# SurfaceControlSystem_RevA.net
KiCad netlist of a schematic drawn in Altium Designer
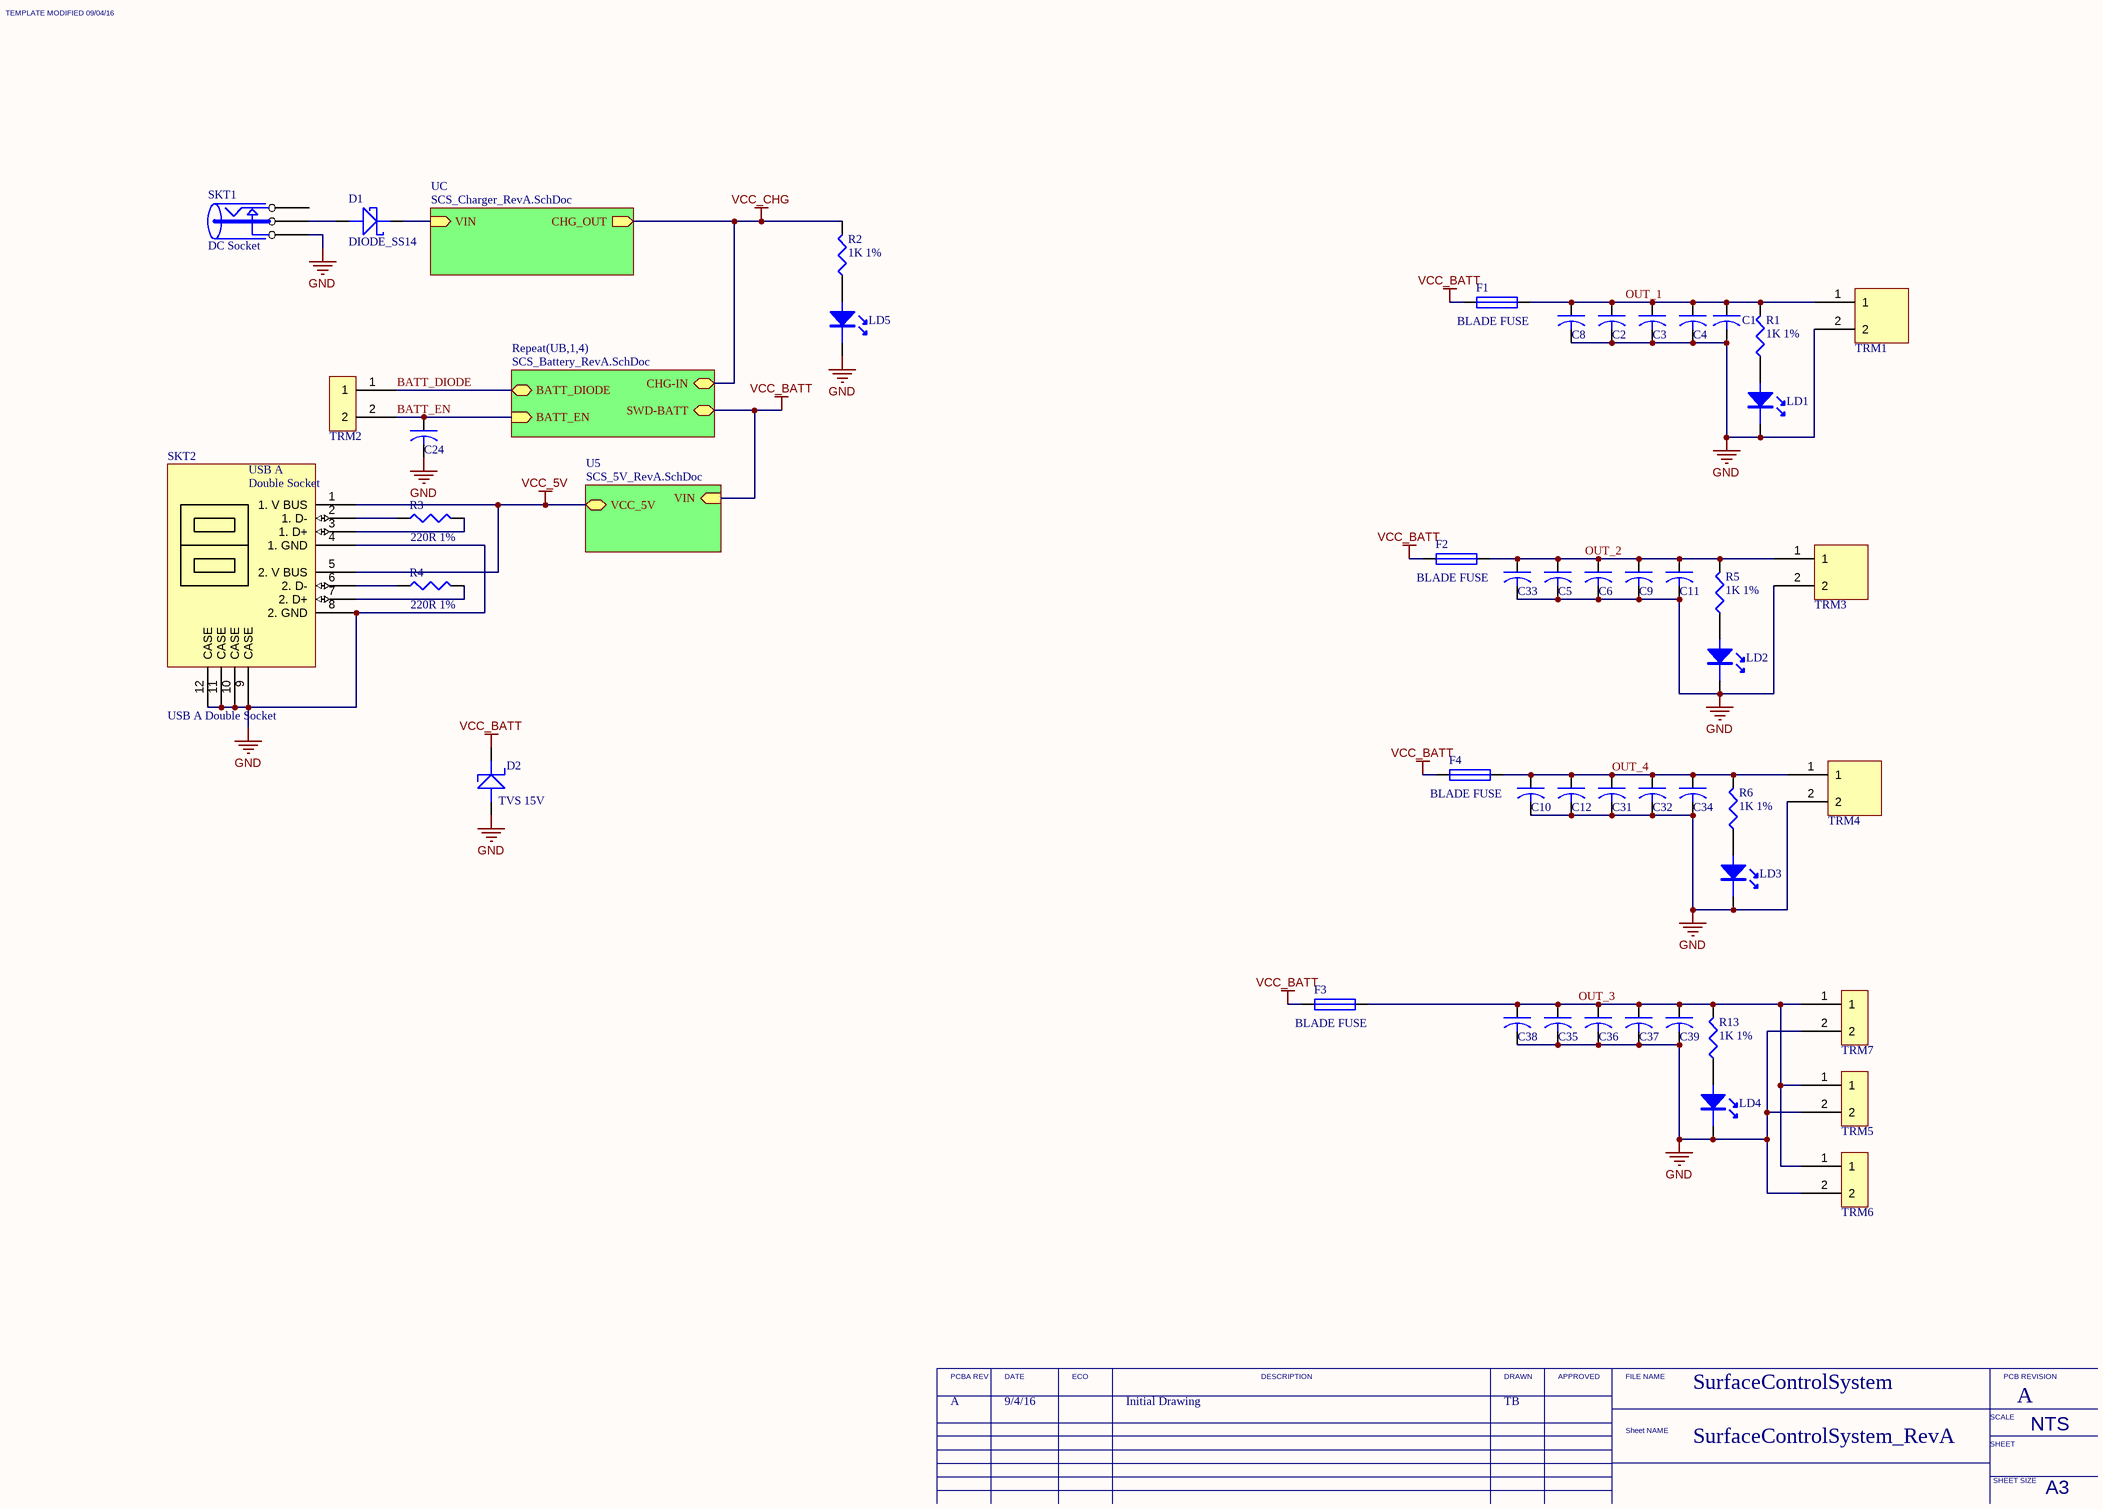
[diagram p0: SurfaceControlSystem_RevA.SchDoc]

(export (version "E")
  (design (tool "Eeschema 10.0.6"))
  (components
    (comp (ref "C1")
      (value "10UF 25V")
      (footprint "1206")
      (description "CAP CER 10UF 25V 10% X5R 1206")
      (fields (field (name "MANUFACTURER") "Murata"))
      (libsource (lib "Caps") (part "CAP_10UF_25V_10%_1206"))
    )
    (comp (ref "C2")
      (value "10UF 25V")
      (footprint "1206")
      (description "CAP CER 10UF 25V 10% X5R 1206")
      (fields (field (name "MANUFACTURER") "Murata"))
      (libsource (lib "Caps") (part "CAP_10UF_25V_10%_1206"))
    )
    (comp (ref "C3")
      (value "10UF 25V")
      (footprint "1206")
      (description "CAP CER 10UF 25V 10% X5R 1206")
      (fields (field (name "MANUFACTURER") "Murata"))
      (libsource (lib "Caps") (part "CAP_10UF_25V_10%_1206"))
    )
    (comp (ref "C4")
      (value "10UF 25V")
      (footprint "1206")
      (description "CAP CER 10UF 25V 10% X5R 1206")
      (fields (field (name "MANUFACTURER") "Murata"))
      (libsource (lib "Caps") (part "CAP_10UF_25V_10%_1206"))
    )
    (comp (ref "C5")
      (value "10UF 25V")
      (footprint "1206")
      (description "CAP CER 10UF 25V 10% X5R 1206")
      (fields (field (name "MANUFACTURER") "Murata"))
      (libsource (lib "Caps") (part "CAP_10UF_25V_10%_1206"))
    )
    (comp (ref "C6")
      (value "10UF 25V")
      (footprint "1206")
      (description "CAP CER 10UF 25V 10% X5R 1206")
      (fields (field (name "MANUFACTURER") "Murata"))
      (libsource (lib "Caps") (part "CAP_10UF_25V_10%_1206"))
    )
    (comp (ref "C8")
      (value "100nF 50V")
      (footprint "0603")
      (description "CAP CER 100nF 50V 10% X7R 0603")
      (fields (field (name "MANUFACTURER") "Murata"))
      (libsource (lib "PowerDistributor") (part "CAP_100NF_50V_10%_0603"))
    )
    (comp (ref "C9")
      (value "10UF 25V")
      (footprint "1206")
      (description "CAP CER 10UF 25V 10% X5R 1206")
      (fields (field (name "MANUFACTURER") "Murata"))
      (libsource (lib "Caps") (part "CAP_10UF_25V_10%_1206"))
    )
    (comp (ref "C10")
      (value "100nF 50V")
      (footprint "0603")
      (description "CAP CER 100nF 50V 10% X7R 0603")
      (fields (field (name "MANUFACTURER") "Murata"))
      (libsource (lib "PowerDistributor") (part "CAP_100NF_50V_10%_0603"))
    )
    (comp (ref "C11")
      (value "10UF 25V")
      (footprint "1206")
      (description "CAP CER 10UF 25V 10% X5R 1206")
      (fields (field (name "MANUFACTURER") "Murata"))
      (libsource (lib "Caps") (part "CAP_10UF_25V_10%_1206"))
    )
    (comp (ref "C12")
      (value "10UF 25V")
      (footprint "1206")
      (description "CAP CER 10UF 25V 10% X5R 1206")
      (fields (field (name "MANUFACTURER") "Murata"))
      (libsource (lib "Caps") (part "CAP_10UF_25V_10%_1206"))
    )
    (comp (ref "C24")
      (value "100nF 50V")
      (footprint "0603")
      (description "CAP CER 100nF 50V 10% X7R 0603")
      (fields (field (name "MANUFACTURER") "Murata"))
      (libsource (lib "PowerDistributor") (part "CAP_100NF_50V_10%_0603"))
    )
    (comp (ref "C31")
      (value "10UF 25V")
      (footprint "1206")
      (description "CAP CER 10UF 25V 10% X5R 1206")
      (fields (field (name "MANUFACTURER") "Murata"))
      (libsource (lib "Caps") (part "CAP_10UF_25V_10%_1206"))
    )
    (comp (ref "C32")
      (value "10UF 25V")
      (footprint "1206")
      (description "CAP CER 10UF 25V 10% X5R 1206")
      (fields (field (name "MANUFACTURER") "Murata"))
      (libsource (lib "Caps") (part "CAP_10UF_25V_10%_1206"))
    )
    (comp (ref "C33")
      (value "100nF 50V")
      (footprint "0603")
      (description "CAP CER 100nF 50V 10% X7R 0603")
      (fields (field (name "MANUFACTURER") "Murata"))
      (libsource (lib "PowerDistributor") (part "CAP_100NF_50V_10%_0603"))
    )
    (comp (ref "C34")
      (value "10UF 25V")
      (footprint "1206")
      (description "CAP CER 10UF 25V 10% X5R 1206")
      (fields (field (name "MANUFACTURER") "Murata"))
      (libsource (lib "Caps") (part "CAP_10UF_25V_10%_1206"))
    )
    (comp (ref "C35")
      (value "10UF 25V")
      (footprint "1206")
      (description "CAP CER 10UF 25V 10% X5R 1206")
      (fields (field (name "MANUFACTURER") "Murata"))
      (libsource (lib "Caps") (part "CAP_10UF_25V_10%_1206"))
    )
    (comp (ref "C36")
      (value "10UF 25V")
      (footprint "1206")
      (description "CAP CER 10UF 25V 10% X5R 1206")
      (fields (field (name "MANUFACTURER") "Murata"))
      (libsource (lib "Caps") (part "CAP_10UF_25V_10%_1206"))
    )
    (comp (ref "C37")
      (value "10UF 25V")
      (footprint "1206")
      (description "CAP CER 10UF 25V 10% X5R 1206")
      (fields (field (name "MANUFACTURER") "Murata"))
      (libsource (lib "Caps") (part "CAP_10UF_25V_10%_1206"))
    )
    (comp (ref "C38")
      (value "100nF 50V")
      (footprint "0603")
      (description "CAP CER 100nF 50V 10% X7R 0603")
      (fields (field (name "MANUFACTURER") "Murata"))
      (libsource (lib "PowerDistributor") (part "CAP_100NF_50V_10%_0603"))
    )
    (comp (ref "C39")
      (value "10UF 25V")
      (footprint "1206")
      (description "CAP CER 10UF 25V 10% X5R 1206")
      (fields (field (name "MANUFACTURER") "Murata"))
      (libsource (lib "Caps") (part "CAP_10UF_25V_10%_1206"))
    )
    (comp (ref "D1")
      (value "DIODE_SS14")
      (footprint "DO-214AC")
      (description "Schottky Diode, 1A, 40V SS14")
      (fields (field (name "MANUFACTURER") "Fairchild"))
      (libsource (lib "Semiconductors") (part "DIODE_SS14"))
    )
    (comp (ref "D2")
      (value "TVS 15V")
      (footprint "DO-214AB")
      (description "TVS Diode, 15V")
      (fields (field (name "MANUFACTURER") "LIttlefuse"))
      (libsource (lib "Semiconductors") (part "DIODE_TVS_SMCJ15A"))
    )
    (comp (ref "F1")
      (value "BLADE FUSE")
      (footprint "FUSEHOLDER_BLADE")
      (description "FUSE CLIP BLADE 500V 30A PCB")
      (fields (field (name "MANUFACTURER") "Keystone Electronics"))
      (libsource (lib "Hardware") (part "FUSE_BLADE_500V_30A_PCB"))
    )
    (comp (ref "F2")
      (value "BLADE FUSE")
      (footprint "FUSEHOLDER_BLADE")
      (description "FUSE CLIP BLADE 500V 30A PCB")
      (fields (field (name "MANUFACTURER") "Keystone Electronics"))
      (libsource (lib "Hardware") (part "FUSE_BLADE_500V_30A_PCB"))
    )
    (comp (ref "F3")
      (value "BLADE FUSE")
      (footprint "FUSEHOLDER_BLADE")
      (description "FUSE CLIP BLADE 500V 30A PCB")
      (fields (field (name "MANUFACTURER") "Keystone Electronics"))
      (libsource (lib "Hardware") (part "FUSE_BLADE_500V_30A_PCB"))
    )
    (comp (ref "F4")
      (value "BLADE FUSE")
      (footprint "FUSEHOLDER_BLADE")
      (description "FUSE CLIP BLADE 500V 30A PCB")
      (fields (field (name "MANUFACTURER") "Keystone Electronics"))
      (libsource (lib "Hardware") (part "FUSE_BLADE_500V_30A_PCB"))
    )
    (comp (ref "LD1")
      (value "Green LED 0805")
      (footprint "0805DIODE")
      (description "WL-SMCW SMD CHIP LED WATERCLEAR")
      (fields (field (name "MANUFACTURER") "Wurth"))
      (libsource (lib "Semiconductors") (part "LED_Green_0805"))
    )
    (comp (ref "LD2")
      (value "Green LED 0805")
      (footprint "0805DIODE")
      (description "WL-SMCW SMD CHIP LED WATERCLEAR")
      (fields (field (name "MANUFACTURER") "Wurth"))
      (libsource (lib "Semiconductors") (part "LED_Green_0805"))
    )
    (comp (ref "LD3")
      (value "Green LED 0805")
      (footprint "0805DIODE")
      (description "WL-SMCW SMD CHIP LED WATERCLEAR")
      (fields (field (name "MANUFACTURER") "Wurth"))
      (libsource (lib "Semiconductors") (part "LED_Green_0805"))
    )
    (comp (ref "LD4")
      (value "Green LED 0805")
      (footprint "0805DIODE")
      (description "WL-SMCW SMD CHIP LED WATERCLEAR")
      (fields (field (name "MANUFACTURER") "Wurth"))
      (libsource (lib "Semiconductors") (part "LED_Green_0805"))
    )
    (comp (ref "LD5")
      (value "Green LED 0805")
      (footprint "0805DIODE")
      (description "WL-SMCW SMD CHIP LED WATERCLEAR")
      (fields (field (name "MANUFACTURER") "Wurth"))
      (libsource (lib "Semiconductors") (part "LED_Green_0805"))
    )
    (comp (ref "R1")
      (value "1K 1%")
      (footprint "0603")
      (description "Resistor, 1K, 1%, 0603")
      (fields (field (name "MANUFACTURER") "Bourns Inc"))
      (libsource (lib "PowerDistributor") (part "RES_1K_1%_0603"))
    )
    (comp (ref "R2")
      (value "1K 1%")
      (footprint "0603")
      (description "Resistor, 1K, 1%, 0603")
      (fields (field (name "MANUFACTURER") "Bourns Inc"))
      (libsource (lib "PowerDistributor") (part "RES_1K_1%_0603"))
    )
    (comp (ref "R3")
      (value "220R 1%")
      (footprint "0603")
      (description "Resistor, 220R, 1%, 0603")
      (fields (field (name "MANUFACTURER") "Bourns Inc"))
      (libsource (lib "Resistors") (part "RES_220R_1%_0603"))
    )
    (comp (ref "R4")
      (value "220R 1%")
      (footprint "0603")
      (description "Resistor, 220R, 1%, 0603")
      (fields (field (name "MANUFACTURER") "Bourns Inc"))
      (libsource (lib "Resistors") (part "RES_220R_1%_0603"))
    )
    (comp (ref "R5")
      (value "1K 1%")
      (footprint "0603")
      (description "Resistor, 1K, 1%, 0603")
      (fields (field (name "MANUFACTURER") "Bourns Inc"))
      (libsource (lib "PowerDistributor") (part "RES_1K_1%_0603"))
    )
    (comp (ref "R6")
      (value "1K 1%")
      (footprint "0603")
      (description "Resistor, 1K, 1%, 0603")
      (fields (field (name "MANUFACTURER") "Bourns Inc"))
      (libsource (lib "PowerDistributor") (part "RES_1K_1%_0603"))
    )
    (comp (ref "R13")
      (value "1K 1%")
      (footprint "0603")
      (description "Resistor, 1K, 1%, 0603")
      (fields (field (name "MANUFACTURER") "Bourns Inc"))
      (libsource (lib "PowerDistributor") (part "RES_1K_1%_0603"))
    )
    (comp (ref "SKT1")
      (value "DC Socket")
      (footprint "SKT_PWR")
      (libsource (lib "Hardware") (part "SOCKET_DC"))
    )
    (comp (ref "SKT2")
      (value "USB A Double Socket")
      (footprint "USB_A_DoubleSocket")
      (fields (field (name "PARTNO") "P1301"))
      (libsource (lib "Hardware") (part "USB_A_Double"))
    )
    (comp (ref "TRM1")
      (value "2way screw terminal, High current")
      (footprint "TERM_2POS_HORIZ_7.62MM")
      (description "TERM BLOCK 2POS HORIZ 7.62MM T/H")
      (fields (field (name "MANUFACTURER") "Altronics"))
      (libsource (lib "Hardware") (part "TRM_2way_ScrewTerminal_7.62mm"))
    )
    (comp (ref "TRM2")
      (value "Wurth 2way screw terminal")
      (footprint "TERM_2POS_HORIZ_5.08MM")
      (description "TERM BLOCK 2POS HORIZ 5.08MM T/H")
      (fields (field (name "MANUFACTURER") "Wurth Electronics Inc"))
      (libsource (lib "") (part "TRM_2way_ScrewTerminal_1"))
    )
    (comp (ref "TRM3")
      (value "2way screw terminal, High current")
      (footprint "TERM_2POS_HORIZ_7.62MM")
      (description "TERM BLOCK 2POS HORIZ 7.62MM T/H")
      (fields (field (name "MANUFACTURER") "Altronics"))
      (libsource (lib "Hardware") (part "TRM_2way_ScrewTerminal_7.62mm"))
    )
    (comp (ref "TRM4")
      (value "2way screw terminal, High current")
      (footprint "TERM_2POS_HORIZ_7.62MM")
      (description "TERM BLOCK 2POS HORIZ 7.62MM T/H")
      (fields (field (name "MANUFACTURER") "Altronics"))
      (libsource (lib "Hardware") (part "TRM_2way_ScrewTerminal_7.62mm"))
    )
    (comp (ref "TRM5")
      (value "Wurth 2way screw terminal")
      (footprint "TERM_2POS_HORIZ_5.08MM")
      (description "TERM BLOCK 2POS HORIZ 5.08MM T/H")
      (fields (field (name "MANUFACTURER") "Wurth Electronics Inc"))
      (libsource (lib "Hardware") (part "TRM_2way_ScrewTerminal"))
    )
    (comp (ref "TRM6")
      (value "Wurth 2way screw terminal")
      (footprint "TERM_2POS_HORIZ_5.08MM")
      (description "TERM BLOCK 2POS HORIZ 5.08MM T/H")
      (fields (field (name "MANUFACTURER") "Wurth Electronics Inc"))
      (libsource (lib "Hardware") (part "TRM_2way_ScrewTerminal"))
    )
    (comp (ref "TRM7")
      (value "Wurth 2way screw terminal")
      (footprint "TERM_2POS_HORIZ_5.08MM")
      (description "TERM BLOCK 2POS HORIZ 5.08MM T/H")
      (fields (field (name "MANUFACTURER") "Wurth Electronics Inc"))
      (libsource (lib "Hardware") (part "TRM_2way_ScrewTerminal"))
    )
  )
  (nets
    (net (code "1") (name "/BATT_DIODE") (class "Default")
      (node (ref "TRM2") (pin "1") (pinfunction "1_1") (pintype "tri_state"))
    )
    (net (code "2") (name "/BATT_EN") (class "Default")
      (node (ref "C24") (pin "1") (pinfunction "1_1") (pintype "passive"))
      (node (ref "TRM2") (pin "2") (pinfunction "2_2") (pintype "tri_state"))
    )
    (net (code "3") (name "/OUT_1") (class "Default")
      (node (ref "C1") (pin "1") (pinfunction "1_1") (pintype "passive"))
      (node (ref "C2") (pin "1") (pinfunction "1_1") (pintype "passive"))
      (node (ref "C3") (pin "1") (pinfunction "1_1") (pintype "passive"))
      (node (ref "C4") (pin "1") (pinfunction "1_1") (pintype "passive"))
      (node (ref "C8") (pin "1") (pinfunction "1_1") (pintype "passive"))
      (node (ref "F1") (pin "2") (pintype "passive"))
      (node (ref "R1") (pin "2") (pintype "passive"))
      (node (ref "TRM1") (pin "1") (pinfunction "1_1") (pintype "tri_state"))
    )
    (net (code "4") (name "/OUT_2") (class "Default")
      (node (ref "C11") (pin "1") (pinfunction "1_1") (pintype "passive"))
      (node (ref "C33") (pin "1") (pinfunction "1_1") (pintype "passive"))
      (node (ref "C5") (pin "1") (pinfunction "1_1") (pintype "passive"))
      (node (ref "C6") (pin "1") (pinfunction "1_1") (pintype "passive"))
      (node (ref "C9") (pin "1") (pinfunction "1_1") (pintype "passive"))
      (node (ref "F2") (pin "2") (pintype "passive"))
      (node (ref "R5") (pin "2") (pintype "passive"))
      (node (ref "TRM3") (pin "1") (pinfunction "1_1") (pintype "tri_state"))
    )
    (net (code "5") (name "/OUT_3") (class "Default")
      (node (ref "C35") (pin "1") (pinfunction "1_1") (pintype "passive"))
      (node (ref "C36") (pin "1") (pinfunction "1_1") (pintype "passive"))
      (node (ref "C37") (pin "1") (pinfunction "1_1") (pintype "passive"))
      (node (ref "C38") (pin "1") (pinfunction "1_1") (pintype "passive"))
      (node (ref "C39") (pin "1") (pinfunction "1_1") (pintype "passive"))
      (node (ref "F3") (pin "2") (pintype "passive"))
      (node (ref "R13") (pin "2") (pintype "passive"))
      (node (ref "TRM5") (pin "1") (pinfunction "1_1") (pintype "tri_state"))
      (node (ref "TRM6") (pin "1") (pinfunction "1_1") (pintype "tri_state"))
      (node (ref "TRM7") (pin "1") (pinfunction "1_1") (pintype "tri_state"))
    )
    (net (code "6") (name "/OUT_4") (class "Default")
      (node (ref "C10") (pin "1") (pinfunction "1_1") (pintype "passive"))
      (node (ref "C12") (pin "1") (pinfunction "1_1") (pintype "passive"))
      (node (ref "C31") (pin "1") (pinfunction "1_1") (pintype "passive"))
      (node (ref "C32") (pin "1") (pinfunction "1_1") (pintype "passive"))
      (node (ref "C34") (pin "1") (pinfunction "1_1") (pintype "passive"))
      (node (ref "F4") (pin "2") (pintype "passive"))
      (node (ref "R6") (pin "2") (pintype "passive"))
      (node (ref "TRM4") (pin "1") (pinfunction "1_1") (pintype "tri_state"))
    )
    (net (code "7") (name "/VIN") (class "Default")
      (node (ref "D1") (pin "K") (pinfunction "K_K") (pintype "passive"))
    )
    (net (code "8") (name "GND") (class "Default")
      (node (ref "C1") (pin "2") (pinfunction "2_2") (pintype "passive"))
      (node (ref "C10") (pin "2") (pinfunction "2_2") (pintype "passive"))
      (node (ref "C11") (pin "2") (pinfunction "2_2") (pintype "passive"))
      (node (ref "C12") (pin "2") (pinfunction "2_2") (pintype "passive"))
      (node (ref "C2") (pin "2") (pinfunction "2_2") (pintype "passive"))
      (node (ref "C24") (pin "2") (pinfunction "2_2") (pintype "passive"))
      (node (ref "C3") (pin "2") (pinfunction "2_2") (pintype "passive"))
      (node (ref "C31") (pin "2") (pinfunction "2_2") (pintype "passive"))
      (node (ref "C32") (pin "2") (pinfunction "2_2") (pintype "passive"))
      (node (ref "C33") (pin "2") (pinfunction "2_2") (pintype "passive"))
      (node (ref "C34") (pin "2") (pinfunction "2_2") (pintype "passive"))
      (node (ref "C35") (pin "2") (pinfunction "2_2") (pintype "passive"))
      (node (ref "C36") (pin "2") (pinfunction "2_2") (pintype "passive"))
      (node (ref "C37") (pin "2") (pinfunction "2_2") (pintype "passive"))
      (node (ref "C38") (pin "2") (pinfunction "2_2") (pintype "passive"))
      (node (ref "C39") (pin "2") (pinfunction "2_2") (pintype "passive"))
      (node (ref "C4") (pin "2") (pinfunction "2_2") (pintype "passive"))
      (node (ref "C5") (pin "2") (pinfunction "2_2") (pintype "passive"))
      (node (ref "C6") (pin "2") (pinfunction "2_2") (pintype "passive"))
      (node (ref "C8") (pin "2") (pinfunction "2_2") (pintype "passive"))
      (node (ref "C9") (pin "2") (pinfunction "2_2") (pintype "passive"))
      (node (ref "D2") (pin "A") (pinfunction "A_A") (pintype "passive"))
      (node (ref "LD1") (pin "K") (pintype "passive"))
      (node (ref "LD2") (pin "K") (pintype "passive"))
      (node (ref "LD3") (pin "K") (pintype "passive"))
      (node (ref "LD4") (pin "K") (pintype "passive"))
      (node (ref "LD5") (pin "K") (pintype "passive"))
      (node (ref "SKT1") (pin "SW") (pinfunction "SW_SW") (pintype "passive"))
      (node (ref "SKT2") (pin "10") (pinfunction "CASE_10") (pintype "power_in"))
      (node (ref "SKT2") (pin "11") (pinfunction "CASE_11") (pintype "power_in"))
      (node (ref "SKT2") (pin "12") (pinfunction "CASE_12") (pintype "power_in"))
      (node (ref "SKT2") (pin "4") (pinfunction "1._GND_4") (pintype "power_in"))
      (node (ref "SKT2") (pin "8") (pinfunction "2._GND_8") (pintype "power_in"))
      (node (ref "SKT2") (pin "9") (pinfunction "CASE_9") (pintype "power_in"))
      (node (ref "TRM1") (pin "2") (pinfunction "2_2") (pintype "tri_state"))
      (node (ref "TRM3") (pin "2") (pinfunction "2_2") (pintype "tri_state"))
      (node (ref "TRM4") (pin "2") (pinfunction "2_2") (pintype "tri_state"))
      (node (ref "TRM5") (pin "2") (pinfunction "2_2") (pintype "tri_state"))
      (node (ref "TRM6") (pin "2") (pinfunction "2_2") (pintype "tri_state"))
      (node (ref "TRM7") (pin "2") (pinfunction "2_2") (pintype "tri_state"))
    )
    (net (code "9") (name "Net-(D1-PadA)") (class "Default")
      (node (ref "D1") (pin "A") (pinfunction "A_A") (pintype "passive"))
      (node (ref "SKT1") (pin "PIN") (pinfunction "PIN_PIN") (pintype "passive"))
    )
    (net (code "10") (name "Net-(LD1-PadA)") (class "Default")
      (node (ref "LD1") (pin "A") (pintype "passive"))
      (node (ref "R1") (pin "1") (pintype "passive"))
    )
    (net (code "11") (name "Net-(LD2-PadA)") (class "Default")
      (node (ref "LD2") (pin "A") (pintype "passive"))
      (node (ref "R5") (pin "1") (pintype "passive"))
    )
    (net (code "12") (name "Net-(LD3-PadA)") (class "Default")
      (node (ref "LD3") (pin "A") (pintype "passive"))
      (node (ref "R6") (pin "1") (pintype "passive"))
    )
    (net (code "13") (name "Net-(LD4-PadA)") (class "Default")
      (node (ref "LD4") (pin "A") (pintype "passive"))
      (node (ref "R13") (pin "1") (pintype "passive"))
    )
    (net (code "14") (name "Net-(LD5-PadA)") (class "Default")
      (node (ref "LD5") (pin "A") (pintype "passive"))
      (node (ref "R2") (pin "1") (pintype "passive"))
    )
    (net (code "15") (name "Net-(SKT2-1._D+)") (class "Default")
      (node (ref "R3") (pin "1") (pintype "passive"))
      (node (ref "SKT2") (pin "3") (pinfunction "1._D+_3") (pintype "bidirectional"))
    )
    (net (code "16") (name "Net-(SKT2-1._D-)") (class "Default")
      (node (ref "R3") (pin "2") (pintype "passive"))
      (node (ref "SKT2") (pin "2") (pinfunction "1._D-_2") (pintype "bidirectional"))
    )
    (net (code "17") (name "Net-(SKT2-2._D+)") (class "Default")
      (node (ref "R4") (pin "1") (pintype "passive"))
      (node (ref "SKT2") (pin "7") (pinfunction "2._D+_7") (pintype "bidirectional"))
    )
    (net (code "18") (name "Net-(SKT2-2._D-)") (class "Default")
      (node (ref "R4") (pin "2") (pintype "passive"))
      (node (ref "SKT2") (pin "6") (pinfunction "2._D-_6") (pintype "bidirectional"))
    )
    (net (code "19") (name "VCC_5V") (class "Default")
      (node (ref "SKT2") (pin "1") (pinfunction "1._V_BUS_1") (pintype "power_in"))
      (node (ref "SKT2") (pin "5") (pinfunction "2._V_BUS_5") (pintype "power_in"))
    )
    (net (code "20") (name "VCC_BATT") (class "Default")
      (node (ref "D2") (pin "K") (pinfunction "K_K") (pintype "passive"))
      (node (ref "F1") (pin "1") (pintype "passive"))
      (node (ref "F2") (pin "1") (pintype "passive"))
      (node (ref "F3") (pin "1") (pintype "passive"))
      (node (ref "F4") (pin "1") (pintype "passive"))
    )
    (net (code "21") (name "VCC_CHG") (class "Default") (node (ref "R2") (pin "2") (pintype "passive")))
    (net (code "22") (name "unconnected-(SKT1-PadCOM)") (class "Default")
      (node (ref "SKT1") (pin "COM") (pinfunction "COM_COM") (pintype "passive"))
    )
  )
)
